# 06_RK3128_USB_ADC_Crystal.net
KiCad netlist of a schematic drawn in Altium Designer
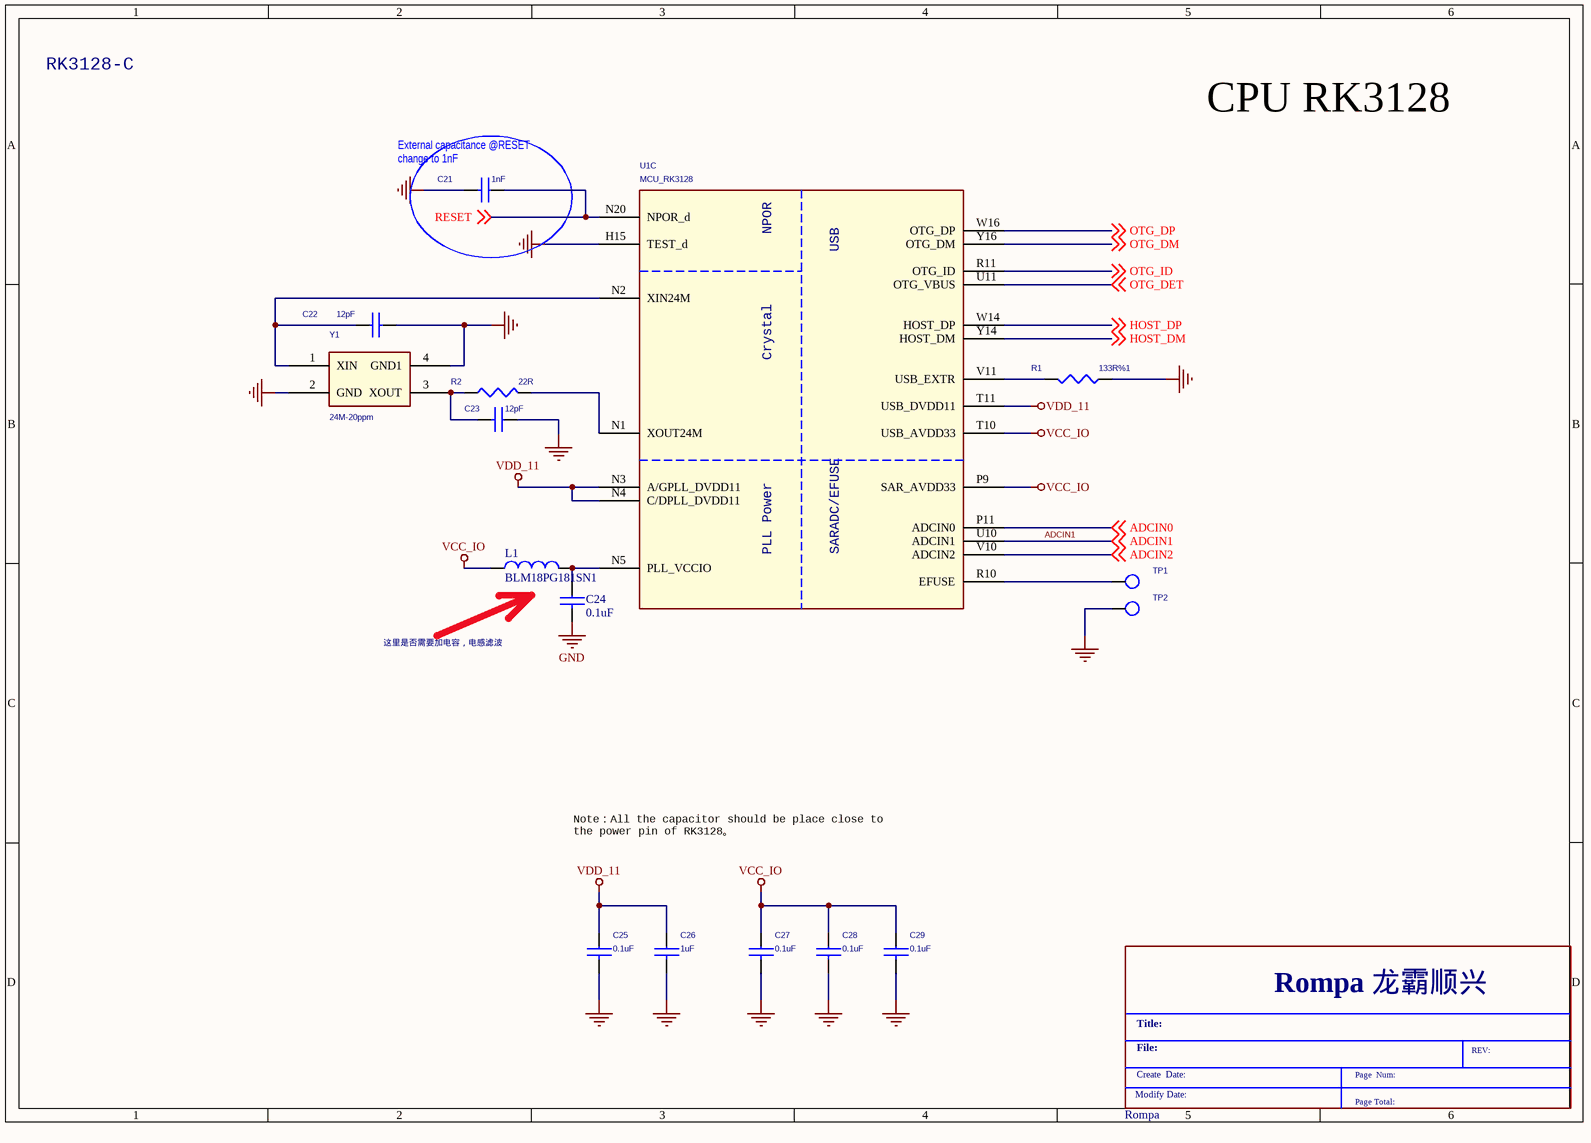
[diagram p0: 06_RK3128_USB_ADC_Crystal.SchDoc]

(export (version "E")
  (design (tool "Eeschema 10.0.6"))
  (components
    (comp (ref "C21")
      (value "1nF")
      (footprint "C0402")
      (description "RoHS CHIP CAP 1nF +10/-10% X5R")
      (libsource (lib "*") (part "CAP NP"))
    )
    (comp (ref "C22") (value "12pF") (footprint "C0402") (libsource (lib "*") (part "CAP NP")))
    (comp (ref "C23") (value "12pF") (footprint "C0402") (libsource (lib "*") (part "CAP NP")))
    (comp (ref "C24")
      (value "0.1uF")
      (footprint "C0402")
      (libsource (lib "RK3128_BETA_V03_20151231_Library") (part "CAP NP"))
    )
    (comp (ref "C25")
      (value "0.1uF")
      (footprint "C0402")
      (description "RoHS CHIP CAP 0.1uF +10/-10% X7R")
      (libsource (lib "*") (part "CAP NP"))
    )
    (comp (ref "C26")
      (value "1uF")
      (footprint "C0402")
      (description "RoHS CHIP CAP 1uF +10/-10% X7R")
      (libsource (lib "*") (part "CAP NP"))
    )
    (comp (ref "C27")
      (value "0.1uF")
      (footprint "C0402")
      (description "RoHS CHIP CAP 0.1uF +10/-10% X7R")
      (libsource (lib "*") (part "CAP NP"))
    )
    (comp (ref "C28")
      (value "0.1uF")
      (footprint "C0402")
      (description "RoHS CHIP CAP 0.1uF +10/-10% X7R")
      (libsource (lib "*") (part "CAP NP"))
    )
    (comp (ref "C29")
      (value "0.1uF")
      (footprint "C0402")
      (description "RoHS CHIP CAP 0.1uF +10/-10% X7R")
      (libsource (lib "*") (part "CAP NP"))
    )
    (comp (ref "L1")
      (value "BLM18PG181SN1")
      (footprint "L0603")
      (description "FERRITE BEAD 180 OHM 0603 1LN")
      (fields (field (name "PUBLISHER") "Altium Limited"))
      (libsource (lib "Miscellaneous Devices") (part "Inductor"))
    )
    (comp (ref "R1")
      (value "133R%1")
      (footprint "R0402")
      (description "ROHS CHIP RES 43.2R 1/16W 1%")
      (libsource (lib "*") (part "RES 1B"))
    )
    (comp (ref "R2") (value "22R") (footprint "R0402") (libsource (lib "*") (part "RES 1B")))
    (comp (ref "TP1") (value "TEST") (footprint "TEST") (libsource (lib "*") (part "TESTPOINT1_0")))
    (comp (ref "TP2") (value "TEST") (footprint "TEST") (libsource (lib "*") (part "TESTPOINT1_0")))
    (comp (ref "U1")
      (value "MCU_RK3128")
      (footprint "BGA316-14X14-0.65")
      (libsource (lib "*") (part "MCU_RK3128"))
    )
    (comp (ref "Y1") (value "24M-20ppm") (footprint "CRY-3225") (libsource (lib "*") (part "CRYSTAL-4_0")))
  )
  (nets
    (net (code "1") (name "ADCIN0") (class "Default")
      (node (ref "U1") (pin "P11") (pinfunction "ADCIN0_P11") (pintype "passive"))
    )
    (net (code "2") (name "ADCIN1") (class "Default")
      (node (ref "U1") (pin "U10") (pinfunction "ADCIN1_U10") (pintype "passive"))
    )
    (net (code "3") (name "ADCIN2") (class "Default")
      (node (ref "U1") (pin "V10") (pinfunction "ADCIN2_V10") (pintype "passive"))
    )
    (net (code "4") (name "GND") (class "Default")
      (node (ref "C21") (pin "2") (pinfunction "2_2") (pintype "passive"))
      (node (ref "C22") (pin "2") (pinfunction "2_2") (pintype "passive"))
      (node (ref "C23") (pin "1") (pinfunction "1_1") (pintype "passive"))
      (node (ref "C24") (pin "2") (pinfunction "2_2") (pintype "passive"))
      (node (ref "C25") (pin "2") (pinfunction "2_2") (pintype "passive"))
      (node (ref "C26") (pin "2") (pinfunction "2_2") (pintype "passive"))
      (node (ref "C27") (pin "2") (pinfunction "2_2") (pintype "passive"))
      (node (ref "C28") (pin "2") (pinfunction "2_2") (pintype "passive"))
      (node (ref "C29") (pin "2") (pinfunction "2_2") (pintype "passive"))
      (node (ref "R1") (pin "1") (pinfunction "1_1") (pintype "passive"))
      (node (ref "TP2") (pin "1") (pinfunction "1_1") (pintype "passive"))
      (node (ref "U1") (pin "H15") (pinfunction "TEST_d_H15") (pintype "passive"))
      (node (ref "Y1") (pin "2") (pinfunction "GND_2") (pintype "passive"))
      (node (ref "Y1") (pin "4") (pinfunction "GND1_4") (pintype "passive"))
    )
    (net (code "5") (name "HOST_DM") (class "Default")
      (node (ref "U1") (pin "Y14") (pinfunction "HOST_DM_Y14") (pintype "passive"))
    )
    (net (code "6") (name "HOST_DP") (class "Default")
      (node (ref "U1") (pin "W14") (pinfunction "HOST_DP_W14") (pintype "passive"))
    )
    (net (code "7") (name "Net-(U1C-EFUSE)") (class "Default")
      (node (ref "TP1") (pin "1") (pinfunction "1_1") (pintype "passive"))
      (node (ref "U1") (pin "R10") (pinfunction "EFUSE_R10") (pintype "passive"))
    )
    (net (code "8") (name "Net-(U1C-PLL_VCCIO)") (class "Default")
      (node (ref "C24") (pin "1") (pinfunction "1_1") (pintype "passive"))
      (node (ref "L1") (pin "2") (pinfunction "2_2") (pintype "passive"))
      (node (ref "U1") (pin "N5") (pinfunction "PLL_VCCIO_N5") (pintype "passive"))
    )
    (net (code "9") (name "Net-(U1C-USB_EXTR)") (class "Default")
      (node (ref "R1") (pin "2") (pinfunction "2_2") (pintype "passive"))
      (node (ref "U1") (pin "V11") (pinfunction "USB_EXTR_V11") (pintype "passive"))
    )
    (net (code "10") (name "Net-(U1C-XIN24M)") (class "Default")
      (node (ref "C22") (pin "1") (pinfunction "1_1") (pintype "passive"))
      (node (ref "U1") (pin "N2") (pinfunction "XIN24M_N2") (pintype "passive"))
      (node (ref "Y1") (pin "1") (pinfunction "XIN_1") (pintype "passive"))
    )
    (net (code "11") (name "Net-(U1C-XOUT24M)") (class "Default")
      (node (ref "R2") (pin "2") (pinfunction "2_2") (pintype "passive"))
      (node (ref "U1") (pin "N1") (pinfunction "XOUT24M_N1") (pintype "passive"))
    )
    (net (code "12") (name "Net-(Y1-XOUT)") (class "Default")
      (node (ref "C23") (pin "2") (pinfunction "2_2") (pintype "passive"))
      (node (ref "R2") (pin "1") (pinfunction "1_1") (pintype "passive"))
      (node (ref "Y1") (pin "3") (pinfunction "XOUT_3") (pintype "passive"))
    )
    (net (code "13") (name "OTG_DET") (class "Default")
      (node (ref "U1") (pin "U11") (pinfunction "OTG_VBUS_U11") (pintype "passive"))
    )
    (net (code "14") (name "OTG_DM") (class "Default")
      (node (ref "U1") (pin "Y16") (pinfunction "OTG_DM_Y16") (pintype "passive"))
    )
    (net (code "15") (name "OTG_DP") (class "Default")
      (node (ref "U1") (pin "W16") (pinfunction "OTG_DP_W16") (pintype "passive"))
    )
    (net (code "16") (name "OTG_ID") (class "Default")
      (node (ref "U1") (pin "R11") (pinfunction "OTG_ID_R11") (pintype "passive"))
    )
    (net (code "17") (name "RESET") (class "Default")
      (node (ref "C21") (pin "1") (pinfunction "1_1") (pintype "passive"))
      (node (ref "U1") (pin "N20") (pinfunction "NPOR_d_N20") (pintype "passive"))
    )
    (net (code "18") (name "VCC_IO") (class "Default")
      (node (ref "C27") (pin "1") (pinfunction "1_1") (pintype "passive"))
      (node (ref "C28") (pin "1") (pinfunction "1_1") (pintype "passive"))
      (node (ref "C29") (pin "1") (pinfunction "1_1") (pintype "passive"))
      (node (ref "L1") (pin "1") (pinfunction "1_1") (pintype "passive"))
      (node (ref "U1") (pin "P9") (pinfunction "SAR_AVDD33_P9") (pintype "passive"))
      (node (ref "U1") (pin "T10") (pinfunction "USB_AVDD33_T10") (pintype "passive"))
    )
    (net (code "19") (name "VDD_11") (class "Default")
      (node (ref "C25") (pin "1") (pinfunction "1_1") (pintype "passive"))
      (node (ref "C26") (pin "1") (pinfunction "1_1") (pintype "passive"))
      (node (ref "U1") (pin "N3") (pinfunction "A/GPLL_DVDD11_N3") (pintype "passive"))
      (node (ref "U1") (pin "N4") (pinfunction "C/DPLL_DVDD11_N4") (pintype "passive"))
      (node (ref "U1") (pin "T11") (pinfunction "USB_DVDD11_T11") (pintype "passive"))
    )
  )
)
